# untitled.net
KiCad netlist of a schematic drawn in EAGLE
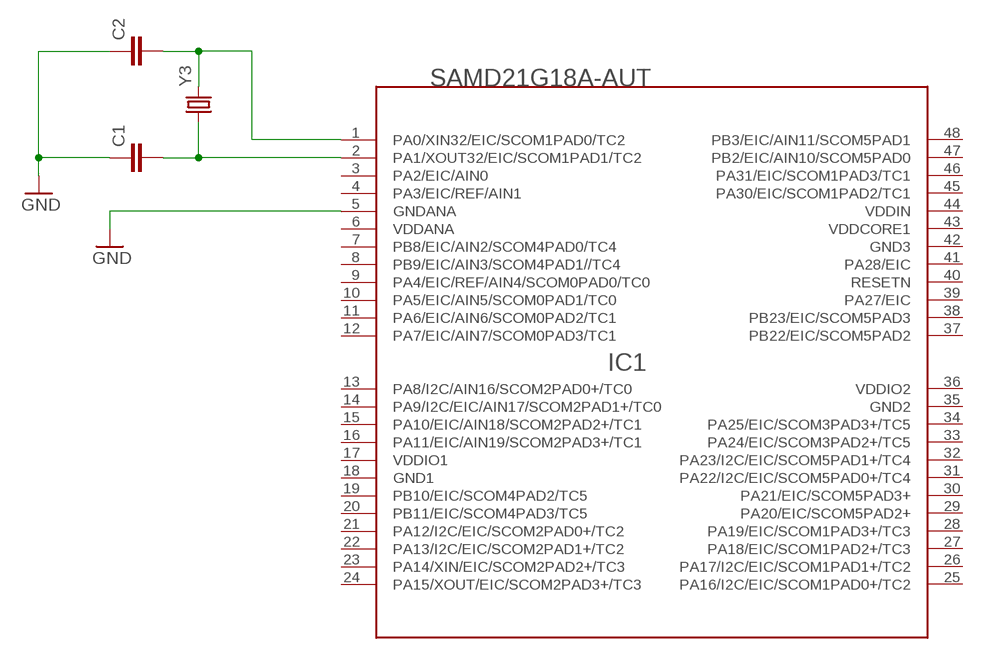
[diagram p0: schematic, sheet 1]

(export (version "E")
  (design (tool "Eeschema 10.0.6"))
  (components
    (comp (ref "C1")
      (value "C-EUC0603")
      (footprint "eagle-import:C0603")
      (libsource (lib "eagle-import") (part "C-EUC0603"))
    )
    (comp (ref "C2")
      (value "C-EUC0603")
      (footprint "eagle-import:C0603")
      (libsource (lib "eagle-import") (part "C-EUC0603"))
    )
    (comp (ref "IC1")
      (value "SAMD21G18A-AUT")
      (footprint "eagle-import:TQFP48-7X7")
      (libsource (lib "eagle-import") (part "1792_SAMD21G18A-AUT"))
    )
    (comp (ref "Y3")
      (value "CRYSTALTXC-7A")
      (footprint "eagle-import:CRYSTAL-TXC-7A")
      (libsource (lib "eagle-import") (part "CRYSTALTXC-7A"))
    )
  )
  (nets
    (net (code "1") (name "/GND1") (class "Default")
      (node (ref "IC1") (pin "18") (pinfunction "GND1_18") (pintype "power_in"))
    )
    (net (code "2") (name "/GND2") (class "Default")
      (node (ref "IC1") (pin "35") (pinfunction "GND2_35") (pintype "power_in"))
    )
    (net (code "3") (name "/GND3") (class "Default")
      (node (ref "IC1") (pin "42") (pinfunction "GND3_42") (pintype "power_in"))
    )
    (net (code "4") (name "/VDDANA") (class "Default")
      (node (ref "IC1") (pin "6") (pinfunction "VDDANA_6") (pintype "power_in"))
    )
    (net (code "5") (name "/VDDIN") (class "Default")
      (node (ref "IC1") (pin "44") (pinfunction "VDDIN_44") (pintype "power_in"))
    )
    (net (code "6") (name "/VDDIO1") (class "Default")
      (node (ref "IC1") (pin "17") (pinfunction "VDDIO1_17") (pintype "power_in"))
    )
    (net (code "7") (name "/VDDIO2") (class "Default")
      (node (ref "IC1") (pin "36") (pinfunction "VDDIO2_36") (pintype "power_in"))
    )
    (net (code "8") (name "GND") (class "Default")
      (node (ref "C1") (pin "1") (pinfunction "1_1") (pintype "passive"))
      (node (ref "C2") (pin "1") (pinfunction "1_1") (pintype "passive"))
      (node (ref "IC1") (pin "5") (pinfunction "GNDANA_5") (pintype "power_in"))
    )
    (net (code "9") (name "Net-(IC1-PA0{slash}XIN32{slash}EIC{slash}SCOM1PAD0{slash}TC2)") (class "Default")
      (node (ref "C2") (pin "2") (pinfunction "2_2") (pintype "passive"))
      (node (ref "IC1") (pin "1") (pinfunction "PA0/XIN32/EIC/SCOM1PAD0/TC2_1") (pintype "bidirectional"))
      (node (ref "Y3") (pin "P$2") (pinfunction "2_P$2") (pintype "passive"))
    )
    (net (code "10") (name "Net-(IC1-PA1{slash}XOUT32{slash}EIC{slash}SCOM1PAD1{slash}TC2)") (class "Default")
      (node (ref "C1") (pin "2") (pinfunction "2_2") (pintype "passive"))
      (node (ref "IC1") (pin "2") (pinfunction "PA1/XOUT32/EIC/SCOM1PAD1/TC2_2") (pintype "bidirectional"))
      (node (ref "Y3") (pin "P$1") (pinfunction "1_P$1") (pintype "passive"))
    )
    (net (code "11") (name "unconnected-(IC1-PA2{slash}EIC{slash}AIN0-Pad3)") (class "Default")
      (node (ref "IC1") (pin "3") (pinfunction "PA2/EIC/AIN0_3") (pintype "bidirectional"))
    )
    (net (code "12") (name "unconnected-(IC1-PA3{slash}EIC{slash}REF{slash}AIN1-Pad4)") (class "Default")
      (node (ref "IC1") (pin "4") (pinfunction "PA3/EIC/REF/AIN1_4") (pintype "bidirectional"))
    )
    (net (code "13") (name "unconnected-(IC1-PA4{slash}EIC{slash}REF{slash}AIN4{slash}SCOM0PAD0{slash}TC0-Pad9)") (class "Default")
      (node (ref "IC1") (pin "9") (pinfunction "PA4/EIC/REF/AIN4/SCOM0PAD0/TC0_9") (pintype "bidirectional"))
    )
    (net (code "14") (name "unconnected-(IC1-PA5{slash}EIC{slash}AIN5{slash}SCOM0PAD1{slash}TC0-Pad10)") (class "Default")
      (node (ref "IC1") (pin "10") (pinfunction "PA5/EIC/AIN5/SCOM0PAD1/TC0_10") (pintype "bidirectional"))
    )
    (net (code "15") (name "unconnected-(IC1-PA6{slash}EIC{slash}AIN6{slash}SCOM0PAD2{slash}TC1-Pad11)") (class "Default")
      (node (ref "IC1") (pin "11") (pinfunction "PA6/EIC/AIN6/SCOM0PAD2/TC1_11") (pintype "bidirectional"))
    )
    (net (code "16") (name "unconnected-(IC1-PA7{slash}EIC{slash}AIN7{slash}SCOM0PAD3{slash}TC1-Pad12)") (class "Default")
      (node (ref "IC1") (pin "12") (pinfunction "PA7/EIC/AIN7/SCOM0PAD3/TC1_12") (pintype "bidirectional"))
    )
    (net (code "17") (name "unconnected-(IC1-PA8{slash}I2C{slash}AIN16{slash}SCOM2PAD0+{slash}TC0-Pad13)") (class "Default")
      (node (ref "IC1") (pin "13") (pinfunction "PA8/I2C/AIN16/SCOM2PAD0+/TC0_13") (pintype "bidirectional"))
    )
    (net (code "18") (name "unconnected-(IC1-PA9{slash}I2C{slash}EIC{slash}AIN17{slash}SCOM2PAD1+{slash}TC0-Pad14)") (class "Default")
      (node (ref "IC1") (pin "14") (pinfunction "PA9/I2C/EIC/AIN17/SCOM2PAD1+/TC0_14") (pintype "bidirectional"))
    )
    (net (code "19") (name "unconnected-(IC1-PA10{slash}EIC{slash}AIN18{slash}SCOM2PAD2+{slash}TC1-Pad15)") (class "Default")
      (node (ref "IC1") (pin "15") (pinfunction "PA10/EIC/AIN18/SCOM2PAD2+/TC1_15") (pintype "bidirectional"))
    )
    (net (code "20") (name "unconnected-(IC1-PA11{slash}EIC{slash}AIN19{slash}SCOM2PAD3+{slash}TC1-Pad16)") (class "Default")
      (node (ref "IC1") (pin "16") (pinfunction "PA11/EIC/AIN19/SCOM2PAD3+/TC1_16") (pintype "bidirectional"))
    )
    (net (code "21") (name "unconnected-(IC1-PA12{slash}I2C{slash}EIC{slash}SCOM2PAD0+{slash}TC2-Pad21)") (class "Default")
      (node (ref "IC1") (pin "21") (pinfunction "PA12/I2C/EIC/SCOM2PAD0+/TC2_21") (pintype "bidirectional"))
    )
    (net (code "22") (name "unconnected-(IC1-PA13{slash}I2C{slash}EIC{slash}SCOM2PAD1+{slash}TC2-Pad22)") (class "Default")
      (node (ref "IC1") (pin "22") (pinfunction "PA13/I2C/EIC/SCOM2PAD1+/TC2_22") (pintype "bidirectional"))
    )
    (net (code "23") (name "unconnected-(IC1-PA14{slash}XIN{slash}EIC{slash}SCOM2PAD2+{slash}TC3-Pad23)") (class "Default")
      (node (ref "IC1") (pin "23") (pinfunction "PA14/XIN/EIC/SCOM2PAD2+/TC3_23") (pintype "bidirectional"))
    )
    (net (code "24") (name "unconnected-(IC1-PA15{slash}XOUT{slash}EIC{slash}SCOM2PAD3+{slash}TC3-Pad24)") (class "Default")
      (node (ref "IC1") (pin "24") (pinfunction "PA15/XOUT/EIC/SCOM2PAD3+/TC3_24") (pintype "bidirectional"))
    )
    (net (code "25") (name "unconnected-(IC1-PA16{slash}I2C{slash}EIC{slash}SCOM1PAD0+{slash}TC2-Pad25)") (class "Default")
      (node (ref "IC1") (pin "25") (pinfunction "PA16/I2C/EIC/SCOM1PAD0+/TC2_25") (pintype "bidirectional"))
    )
    (net (code "26") (name "unconnected-(IC1-PA17{slash}I2C{slash}EIC{slash}SCOM1PAD1+{slash}TC2-Pad26)") (class "Default")
      (node (ref "IC1") (pin "26") (pinfunction "PA17/I2C/EIC/SCOM1PAD1+/TC2_26") (pintype "bidirectional"))
    )
    (net (code "27") (name "unconnected-(IC1-PA18{slash}EIC{slash}SCOM1PAD2+{slash}TC3-Pad27)") (class "Default")
      (node (ref "IC1") (pin "27") (pinfunction "PA18/EIC/SCOM1PAD2+/TC3_27") (pintype "bidirectional"))
    )
    (net (code "28") (name "unconnected-(IC1-PA19{slash}EIC{slash}SCOM1PAD3+{slash}TC3-Pad28)") (class "Default")
      (node (ref "IC1") (pin "28") (pinfunction "PA19/EIC/SCOM1PAD3+/TC3_28") (pintype "bidirectional"))
    )
    (net (code "29") (name "unconnected-(IC1-PA20{slash}EIC{slash}SCOM5PAD2+-Pad29)") (class "Default")
      (node (ref "IC1") (pin "29") (pinfunction "PA20/EIC/SCOM5PAD2+_29") (pintype "bidirectional"))
    )
    (net (code "30") (name "unconnected-(IC1-PA21{slash}EIC{slash}SCOM5PAD3+-Pad30)") (class "Default")
      (node (ref "IC1") (pin "30") (pinfunction "PA21/EIC/SCOM5PAD3+_30") (pintype "bidirectional"))
    )
    (net (code "31") (name "unconnected-(IC1-PA22{slash}I2C{slash}EIC{slash}SCOM5PAD0+{slash}TC4-Pad31)") (class "Default")
      (node (ref "IC1") (pin "31") (pinfunction "PA22/I2C/EIC/SCOM5PAD0+/TC4_31") (pintype "bidirectional"))
    )
    (net (code "32") (name "unconnected-(IC1-PA23{slash}I2C{slash}EIC{slash}SCOM5PAD1+{slash}TC4-Pad32)") (class "Default")
      (node (ref "IC1") (pin "32") (pinfunction "PA23/I2C/EIC/SCOM5PAD1+/TC4_32") (pintype "bidirectional"))
    )
    (net (code "33") (name "unconnected-(IC1-PA24{slash}EIC{slash}SCOM3PAD2+{slash}TC5-Pad33)") (class "Default")
      (node (ref "IC1") (pin "33") (pinfunction "PA24/EIC/SCOM3PAD2+/TC5_33") (pintype "bidirectional"))
    )
    (net (code "34") (name "unconnected-(IC1-PA25{slash}EIC{slash}SCOM3PAD3+{slash}TC5-Pad34)") (class "Default")
      (node (ref "IC1") (pin "34") (pinfunction "PA25/EIC/SCOM3PAD3+/TC5_34") (pintype "bidirectional"))
    )
    (net (code "35") (name "unconnected-(IC1-PA27{slash}EIC-Pad39)") (class "Default")
      (node (ref "IC1") (pin "39") (pinfunction "PA27/EIC_39") (pintype "bidirectional"))
    )
    (net (code "36") (name "unconnected-(IC1-PA28{slash}EIC-Pad41)") (class "Default")
      (node (ref "IC1") (pin "41") (pinfunction "PA28/EIC_41") (pintype "bidirectional"))
    )
    (net (code "37") (name "unconnected-(IC1-PA30{slash}EIC{slash}SCOM1PAD2{slash}TC1-Pad45)") (class "Default")
      (node (ref "IC1") (pin "45") (pinfunction "PA30/EIC/SCOM1PAD2/TC1_45") (pintype "bidirectional"))
    )
    (net (code "38") (name "unconnected-(IC1-PA31{slash}EIC{slash}SCOM1PAD3{slash}TC1-Pad46)") (class "Default")
      (node (ref "IC1") (pin "46") (pinfunction "PA31/EIC/SCOM1PAD3/TC1_46") (pintype "bidirectional"))
    )
    (net (code "39") (name "unconnected-(IC1-PB2{slash}EIC{slash}AIN10{slash}SCOM5PAD0-Pad47)") (class "Default")
      (node (ref "IC1") (pin "47") (pinfunction "PB2/EIC/AIN10/SCOM5PAD0_47") (pintype "bidirectional"))
    )
    (net (code "40") (name "unconnected-(IC1-PB3{slash}EIC{slash}AIN11{slash}SCOM5PAD1-Pad48)") (class "Default")
      (node (ref "IC1") (pin "48") (pinfunction "PB3/EIC/AIN11/SCOM5PAD1_48") (pintype "bidirectional"))
    )
    (net (code "41") (name "unconnected-(IC1-PB8{slash}EIC{slash}AIN2{slash}SCOM4PAD0{slash}TC4-Pad7)") (class "Default")
      (node (ref "IC1") (pin "7") (pinfunction "PB8/EIC/AIN2/SCOM4PAD0/TC4_7") (pintype "bidirectional"))
    )
    (net (code "42") (name "unconnected-(IC1-PB9{slash}EIC{slash}AIN3{slash}SCOM4PAD1{slash}{slash}TC4-Pad8)") (class "Default")
      (node (ref "IC1") (pin "8") (pinfunction "PB9/EIC/AIN3/SCOM4PAD1//TC4_8") (pintype "bidirectional"))
    )
    (net (code "43") (name "unconnected-(IC1-PB10{slash}EIC{slash}SCOM4PAD2{slash}TC5-Pad19)") (class "Default")
      (node (ref "IC1") (pin "19") (pinfunction "PB10/EIC/SCOM4PAD2/TC5_19") (pintype "bidirectional"))
    )
    (net (code "44") (name "unconnected-(IC1-PB11{slash}EIC{slash}SCOM4PAD3{slash}TC5-Pad20)") (class "Default")
      (node (ref "IC1") (pin "20") (pinfunction "PB11/EIC/SCOM4PAD3/TC5_20") (pintype "bidirectional"))
    )
    (net (code "45") (name "unconnected-(IC1-PB22{slash}EIC{slash}SCOM5PAD2-Pad37)") (class "Default")
      (node (ref "IC1") (pin "37") (pinfunction "PB22/EIC/SCOM5PAD2_37") (pintype "bidirectional"))
    )
    (net (code "46") (name "unconnected-(IC1-PB23{slash}EIC{slash}SCOM5PAD3-Pad38)") (class "Default")
      (node (ref "IC1") (pin "38") (pinfunction "PB23/EIC/SCOM5PAD3_38") (pintype "bidirectional"))
    )
    (net (code "47") (name "unconnected-(IC1-RESETN-Pad40)") (class "Default")
      (node (ref "IC1") (pin "40") (pinfunction "RESETN_40") (pintype "bidirectional"))
    )
    (net (code "48") (name "unconnected-(IC1-VDDCORE1-Pad43)") (class "Default")
      (node (ref "IC1") (pin "43") (pinfunction "VDDCORE1_43") (pintype "input"))
    )
  )
)
